# DC-Boost_12-24v.net
KiCad netlist of a schematic drawn in EAGLE
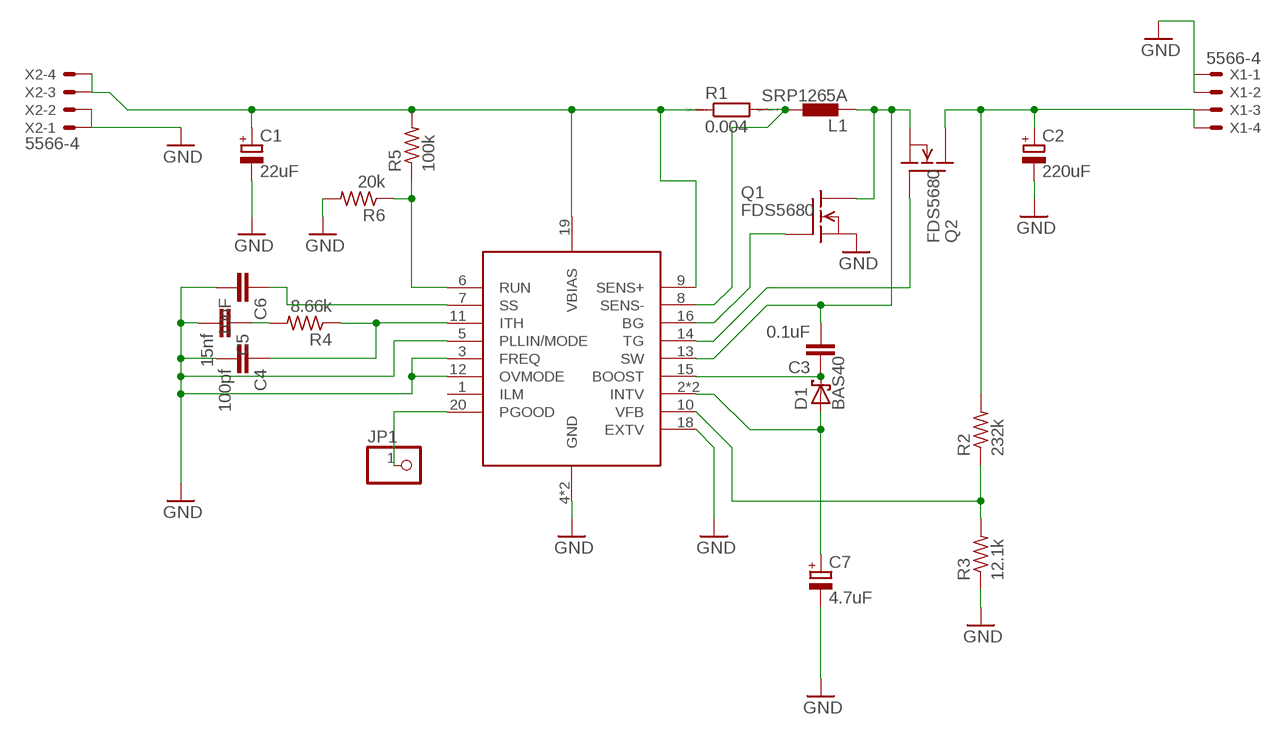
[diagram p0: schematic, sheet 1]

(export (version "E")
  (design (tool "Eeschema 10.0.6"))
  (components
    (comp (ref "C1")
      (value "22uF")
      (footprint "eagle-import:E2-5")
      (libsource (lib "eagle-import") (part "CPOL-EUE2-5"))
    )
    (comp (ref "C2")
      (value "220uF")
      (footprint "eagle-import:TT5D10")
      (libsource (lib "eagle-import") (part "CPOL-EUTT5D10"))
    )
    (comp (ref "C3")
      (value "0.1uF")
      (footprint "eagle-import:C5B3")
      (libsource (lib "eagle-import") (part "C5/3"))
    )
    (comp (ref "C4")
      (value "100pf")
      (footprint "eagle-import:C5B3.5")
      (libsource (lib "eagle-import") (part "C5/3.5"))
    )
    (comp (ref "C5")
      (value "15nf")
      (footprint "eagle-import:C2.5-3")
      (libsource (lib "eagle-import") (part "C2,5-3"))
    )
    (comp (ref "C6")
      (value "10nF")
      (footprint "eagle-import:C5B3")
      (libsource (lib "eagle-import") (part "C5/3"))
    )
    (comp (ref "C7")
      (value "4.7uF")
      (footprint "eagle-import:E2-5")
      (libsource (lib "eagle-import") (part "CPOL-EUE2-5"))
    )
    (comp (ref "D1")
      (value "BAS40")
      (footprint "eagle-import:SOT23")
      (libsource (lib "eagle-import") (part "BAS40"))
    )
    (comp (ref "JP1")
      (value "PINHD-1X1")
      (footprint "eagle-import:1X01")
      (libsource (lib "eagle-import") (part "PINHD-1X1"))
    )
    (comp (ref "L1")
      (value "SRP1265A")
      (footprint "eagle-import:SRP1265")
      (libsource (lib "eagle-import") (part "SRP1265A"))
    )
    (comp (ref "Q1")
      (value "FDS5680")
      (footprint "eagle-import:SO-8")
      (libsource (lib "eagle-import") (part "FDS5680"))
    )
    (comp (ref "Q2")
      (value "FDS5680")
      (footprint "eagle-import:SO-8")
      (libsource (lib "eagle-import") (part "FDS5680"))
    )
    (comp (ref "R1")
      (value "0.004")
      (footprint "eagle-import:R2512")
      (libsource (lib "eagle-import") (part "RR2512"))
    )
    (comp (ref "R2")
      (value "232k")
      (footprint "eagle-import:0207_10")
      (libsource (lib "eagle-import") (part "R-US_0207/10"))
    )
    (comp (ref "R3")
      (value "12.1k")
      (footprint "eagle-import:0207_10")
      (libsource (lib "eagle-import") (part "R-US_0207/10"))
    )
    (comp (ref "R4")
      (value "8.66k")
      (footprint "eagle-import:0207_10")
      (libsource (lib "eagle-import") (part "R-US_0207/10"))
    )
    (comp (ref "R5")
      (value "100k")
      (footprint "eagle-import:0207_10")
      (libsource (lib "eagle-import") (part "R-US_0207/10"))
    )
    (comp (ref "R6")
      (value "20k")
      (footprint "eagle-import:0207_10")
      (libsource (lib "eagle-import") (part "R-US_0207/10"))
    )
    (comp (ref "U$1")
      (value "LTC3769")
      (footprint "eagle-import:TSSOP-20")
      (libsource (lib "eagle-import") (part "LTC3769"))
    )
    (comp (ref "X1")
      (value "5566-4")
      (footprint "eagle-import:5566-4")
      (libsource (lib "eagle-import") (part "5566-4"))
    )
    (comp (ref "X2")
      (value "5566-4")
      (footprint "eagle-import:5566-4")
      (libsource (lib "eagle-import") (part "5566-4"))
    )
  )
  (nets
    (net (code "1") (name "GND") (class "Default")
      (node (ref "C1") (pin "-") (pinfunction "-_-") (pintype "passive"))
      (node (ref "C2") (pin "-") (pinfunction "-_-") (pintype "passive"))
      (node (ref "C4") (pin "2") (pinfunction "2_2") (pintype "passive"))
      (node (ref "C5") (pin "2") (pinfunction "2_2") (pintype "passive"))
      (node (ref "C6") (pin "2") (pinfunction "2_2") (pintype "passive"))
      (node (ref "C7") (pin "-") (pinfunction "-_-") (pintype "passive"))
      (node (ref "Q1") (pin "1") (pinfunction "S_1") (pintype "passive"))
      (node (ref "Q1") (pin "2") (pinfunction "S_2") (pintype "passive"))
      (node (ref "Q1") (pin "3") (pinfunction "S_3") (pintype "passive"))
      (node (ref "R3") (pin "1") (pinfunction "1_1") (pintype "passive"))
      (node (ref "R6") (pin "2") (pinfunction "2_2") (pintype "passive"))
      (node (ref "U$1") (pin "12") (pinfunction "OVMODE_12") (pintype "bidirectional"))
      (node (ref "U$1") (pin "18") (pinfunction "EXTV_18") (pintype "bidirectional"))
      (node (ref "U$1") (pin "21") (pinfunction "GND_21") (pintype "bidirectional"))
      (node (ref "U$1") (pin "3") (pinfunction "FREQ_3") (pintype "bidirectional"))
      (node (ref "U$1") (pin "4") (pinfunction "GND_4") (pintype "bidirectional"))
      (node (ref "U$1") (pin "5") (pinfunction "PLLIN/MODE_5") (pintype "bidirectional"))
      (node (ref "X1") (pin "1") (pinfunction "S_1") (pintype "passive"))
      (node (ref "X1") (pin "2") (pinfunction "S_2") (pintype "passive"))
      (node (ref "X2") (pin "1") (pinfunction "S_1") (pintype "passive"))
      (node (ref "X2") (pin "2") (pinfunction "S_2") (pintype "passive"))
    )
    (net (code "2") (name "Net-(C5-Pad1)") (class "Default")
      (node (ref "C5") (pin "1") (pinfunction "1_1") (pintype "passive"))
      (node (ref "R4") (pin "2") (pinfunction "2_2") (pintype "passive"))
    )
    (net (code "3") (name "Net-(D1-A)") (class "Default")
      (node (ref "C7") (pin "+") (pinfunction "+_+") (pintype "passive"))
      (node (ref "D1") (pin "1") (pinfunction "A_1") (pintype "passive"))
      (node (ref "U$1") (pin "17") (pinfunction "INTV_17") (pintype "bidirectional"))
      (node (ref "U$1") (pin "2") (pinfunction "INTV_2") (pintype "bidirectional"))
    )
    (net (code "4") (name "Net-(D1-C)") (class "Default")
      (node (ref "C3") (pin "1") (pinfunction "1_1") (pintype "passive"))
      (node (ref "D1") (pin "3") (pinfunction "C_3") (pintype "passive"))
      (node (ref "U$1") (pin "15") (pinfunction "BOOST_15") (pintype "bidirectional"))
    )
    (net (code "5") (name "Net-(L1-1)") (class "Default")
      (node (ref "C3") (pin "2") (pinfunction "2_2") (pintype "passive"))
      (node (ref "L1") (pin "P$1") (pinfunction "1_P$1") (pintype "passive"))
      (node (ref "Q1") (pin "5") (pinfunction "D_5") (pintype "passive"))
      (node (ref "Q1") (pin "6") (pinfunction "D_6") (pintype "passive"))
      (node (ref "Q1") (pin "7") (pinfunction "D_7") (pintype "passive"))
      (node (ref "Q1") (pin "8") (pinfunction "D_8") (pintype "passive"))
      (node (ref "Q2") (pin "1") (pinfunction "S_1") (pintype "passive"))
      (node (ref "Q2") (pin "2") (pinfunction "S_2") (pintype "passive"))
      (node (ref "Q2") (pin "3") (pinfunction "S_3") (pintype "passive"))
      (node (ref "U$1") (pin "13") (pinfunction "SW_13") (pintype "bidirectional"))
    )
    (net (code "6") (name "Net-(L1-2)") (class "Default")
      (node (ref "L1") (pin "P$3") (pinfunction "2_P$3") (pintype "passive"))
      (node (ref "R1") (pin "2") (pinfunction "2_2") (pintype "passive"))
      (node (ref "U$1") (pin "8") (pinfunction "SENS-_8") (pintype "bidirectional"))
    )
    (net (code "7") (name "Net-(Q1-G)") (class "Default")
      (node (ref "Q1") (pin "4") (pinfunction "G_4") (pintype "passive"))
      (node (ref "U$1") (pin "16") (pinfunction "BG_16") (pintype "bidirectional"))
    )
    (net (code "8") (name "Net-(Q2-G)") (class "Default")
      (node (ref "Q2") (pin "4") (pinfunction "G_4") (pintype "passive"))
      (node (ref "U$1") (pin "14") (pinfunction "TG_14") (pintype "bidirectional"))
    )
    (net (code "9") (name "Net-(U$1-ITH)") (class "Default")
      (node (ref "C4") (pin "1") (pinfunction "1_1") (pintype "passive"))
      (node (ref "R4") (pin "1") (pinfunction "1_1") (pintype "passive"))
      (node (ref "U$1") (pin "11") (pinfunction "ITH_11") (pintype "bidirectional"))
    )
    (net (code "10") (name "Net-(U$1-PGOOD)") (class "Default")
      (node (ref "JP1") (pin "1") (pinfunction "1_1") (pintype "passive"))
      (node (ref "U$1") (pin "20") (pinfunction "PGOOD_20") (pintype "bidirectional"))
    )
    (net (code "11") (name "Net-(U$1-RUN)") (class "Default")
      (node (ref "R5") (pin "1") (pinfunction "1_1") (pintype "passive"))
      (node (ref "R6") (pin "1") (pinfunction "1_1") (pintype "passive"))
      (node (ref "U$1") (pin "6") (pinfunction "RUN_6") (pintype "bidirectional"))
    )
    (net (code "12") (name "Net-(U$1-SENS+)") (class "Default")
      (node (ref "C1") (pin "+") (pinfunction "+_+") (pintype "passive"))
      (node (ref "R1") (pin "1") (pinfunction "1_1") (pintype "passive"))
      (node (ref "R5") (pin "2") (pinfunction "2_2") (pintype "passive"))
      (node (ref "U$1") (pin "19") (pinfunction "VBIAS_19") (pintype "bidirectional"))
      (node (ref "U$1") (pin "9") (pinfunction "SENS+_9") (pintype "bidirectional"))
      (node (ref "X2") (pin "3") (pinfunction "S_3") (pintype "passive"))
      (node (ref "X2") (pin "4") (pinfunction "S_4") (pintype "passive"))
    )
    (net (code "13") (name "Net-(U$1-SS)") (class "Default")
      (node (ref "C6") (pin "1") (pinfunction "1_1") (pintype "passive"))
      (node (ref "U$1") (pin "7") (pinfunction "SS_7") (pintype "bidirectional"))
    )
    (net (code "14") (name "Net-(U$1-VFB)") (class "Default")
      (node (ref "R2") (pin "1") (pinfunction "1_1") (pintype "passive"))
      (node (ref "R3") (pin "2") (pinfunction "2_2") (pintype "passive"))
      (node (ref "U$1") (pin "10") (pinfunction "VFB_10") (pintype "bidirectional"))
    )
    (net (code "15") (name "Net-(X1C-S)") (class "Default")
      (node (ref "C2") (pin "+") (pinfunction "+_+") (pintype "passive"))
      (node (ref "Q2") (pin "5") (pinfunction "D_5") (pintype "passive"))
      (node (ref "Q2") (pin "6") (pinfunction "D_6") (pintype "passive"))
      (node (ref "Q2") (pin "7") (pinfunction "D_7") (pintype "passive"))
      (node (ref "Q2") (pin "8") (pinfunction "D_8") (pintype "passive"))
      (node (ref "R2") (pin "2") (pinfunction "2_2") (pintype "passive"))
      (node (ref "X1") (pin "3") (pinfunction "S_3") (pintype "passive"))
      (node (ref "X1") (pin "4") (pinfunction "S_4") (pintype "passive"))
    )
    (net (code "16") (name "unconnected-(U$1-ILM-Pad1)") (class "Default")
      (node (ref "U$1") (pin "1") (pinfunction "ILM_1") (pintype "bidirectional"))
    )
  )
)
